# ArduinoUnoShield.net
KiCad netlist of a schematic drawn in Altium Designer
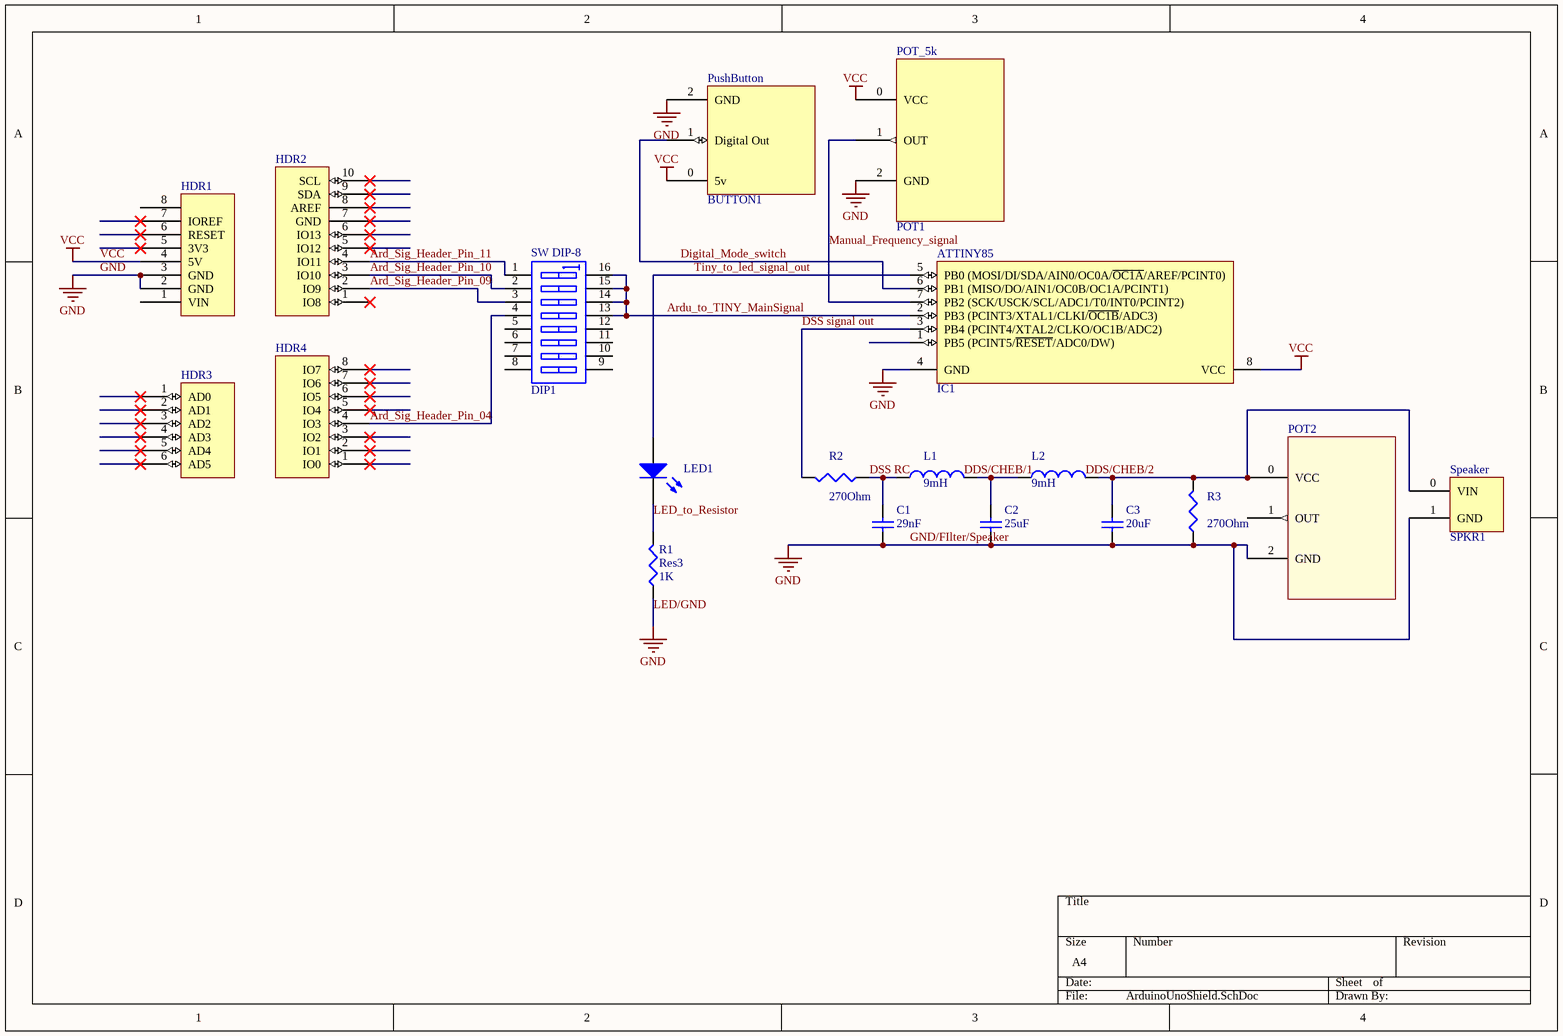
[diagram p0: ArduinoUnoShield.SchDoc]

(export (version "E")
  (design (tool "Eeschema 10.0.6"))
  (components
    (comp (ref "ATTINY85")
      (value "IC1")
      (footprint "DIP-8")
      (fields (field (name "PUBLISHER") "Altium Limited"))
      (libsource (lib "Atmel Microcontroller 8-Bit tinyAVR") (part "ATtiny85-20PU"))
    )
    (comp (ref "C1")
      (value "29nF")
      (footprint "1608[0603]")
      (description "Capacitor (Semiconductor SIM Model)")
      (fields (field (name "Comment") "Cap Semi") (field (name "PUBLISHER") "Altium Limited"))
      (libsource (lib "Miscellaneous Devices") (part "Cap Semi"))
    )
    (comp (ref "C2")
      (value "25uF")
      (footprint "1608[0603]")
      (description "Capacitor (Semiconductor SIM Model)")
      (fields (field (name "Comment") "Cap Semi") (field (name "PUBLISHER") "Altium Limited"))
      (libsource (lib "Miscellaneous Devices") (part "Cap Semi"))
    )
    (comp (ref "C3")
      (value "20uF")
      (footprint "1608[0603]")
      (description "Capacitor (Semiconductor SIM Model)")
      (fields (field (name "Comment") "Cap Semi") (field (name "PUBLISHER") "Altium Limited"))
      (libsource (lib "Miscellaneous Devices") (part "Cap Semi"))
    )
    (comp (ref "HDR1")
      (value "POWER_UNO")
      (footprint "Header 8x1 8.5mm")
      (libsource (lib "Header") (part "POWER_UNO"))
    )
    (comp (ref "HDR2")
      (value "IOH")
      (footprint "Header:Header 10x1 8.5mm")
      (libsource (lib "Header") (part "IOH"))
    )
    (comp (ref "HDR3")
      (value "AD")
      (footprint "Header:Header 6x1 8.5mm")
      (libsource (lib "Header") (part "AD"))
    )
    (comp (ref "HDR4") (value "IOL") (footprint "Header 8x1 8.5mm") (libsource (lib "Header") (part "IOL")))
    (comp (ref "L1")
      (value "9mH")
      (footprint "AXIAL-0.3")
      (description "Inductor")
      (fields (field (name "PUBLISHER") "Altium Limited"))
      (libsource (lib "Miscellaneous Devices") (part "Inductor"))
    )
    (comp (ref "L2")
      (value "9mH")
      (footprint "AXIAL-0.3")
      (description "Inductor")
      (fields (field (name "PUBLISHER") "Altium Limited"))
      (libsource (lib "Miscellaneous Devices") (part "Inductor"))
    )
    (comp (ref "LED1")
      (value "LED1")
      (footprint "LED-1")
      (description "Typical RED GaAs LED")
      (fields (field (name "PUBLISHER") "Altium Limited"))
      (libsource (lib "Miscellaneous Devices") (part "LED1"))
    )
    (comp (ref "POT2")
      (value "Component_1")
      (footprint "POT Footprint_Rev_1")
      (description "5k RES")
      (libsource (lib "PotLib_Rev_5") (part "Component_1"))
    )
    (comp (ref "POT_5k")
      (value "POT1")
      (footprint "POT Footprint_Rev_1")
      (description "5k RES")
      (libsource (lib "PotLib_Rev_5") (part "Component_1"))
    )
    (comp (ref "PushButton")
      (value "BUTTON1")
      (footprint "PushButtonFrame")
      (libsource (lib "Pushbutton_V_5") (part "PushButton"))
    )
    (comp (ref "R1")
      (value "Res3")
      (footprint "J1-0603")
      (description "Resistor")
      (fields (field (name "ALTIUM_VALUE") "1K") (field (name "PUBLISHER") "Altium Limited"))
      (libsource (lib "Miscellaneous Devices") (part "Res3"))
    )
    (comp (ref "R2")
      (value "270Ohm")
      (footprint "J1-0603")
      (description "Resistor")
      (fields (field (name "Comment") "Res3") (field (name "PUBLISHER") "Altium Limited"))
      (libsource (lib "Miscellaneous Devices") (part "Res3"))
    )
    (comp (ref "R3")
      (value "270Ohm")
      (footprint "J1-0603")
      (description "Resistor")
      (fields (field (name "Comment") "Res3") (field (name "PUBLISHER") "Altium Limited"))
      (libsource (lib "Miscellaneous Devices") (part "Res3"))
    )
    (comp (ref "Speaker")
      (value "SPKR1")
      (footprint "PCBComponent_1")
      (libsource (lib "Schlib1_rev_01") (part "Component_1"))
    )
    (comp (ref "SW DIP-8")
      (value "DIP1")
      (footprint "DIP_SW_8WAY_SMD")
      (description "DIP Switch, 8 Position, SPST")
      (fields (field (name "PUBLISHER") "Altium Limited"))
      (libsource (lib "Miscellaneous Devices") (part "SW DIP-8"))
    )
  )
  (nets
    (net (code "2") (name "/Ard_Sig_Header_Pin_04") (class "Default")
      (node (ref "HDR4") (pin "4") (pinfunction "IO3_4") (pintype "bidirectional"))
      (node (ref "SW DIP-8") (pin "4") (pinfunction "A4_4") (pintype "passive"))
    )
    (net (code "3") (name "/Ard_Sig_Header_Pin_09") (class "Default")
      (node (ref "HDR2") (pin "2") (pinfunction "IO9_2") (pintype "bidirectional"))
      (node (ref "SW DIP-8") (pin "3") (pinfunction "A3_3") (pintype "passive"))
    )
    (net (code "4") (name "/Ard_Sig_Header_Pin_10") (class "Default")
      (node (ref "HDR2") (pin "3") (pinfunction "IO10_3") (pintype "bidirectional"))
      (node (ref "SW DIP-8") (pin "2") (pinfunction "A2_2") (pintype "passive"))
    )
    (net (code "5") (name "/Ard_Sig_Header_Pin_11") (class "Default")
      (node (ref "HDR2") (pin "4") (pinfunction "IO11_4") (pintype "bidirectional"))
      (node (ref "SW DIP-8") (pin "1") (pinfunction "A1_1") (pintype "passive"))
    )
    (net (code "6") (name "/Ardu_to_TINY_MainSignal") (class "Default")
      (node (ref "ATTINY85") (pin "2") (pinfunction "PB3_(PCINT3/XTAL1/CLKI/~{OC1B}/ADC3)_2") (pintype "bidirectional"))
      (node (ref "SW DIP-8") (pin "13") (pinfunction "B4_13") (pintype "passive"))
      (node (ref "SW DIP-8") (pin "14") (pinfunction "B3_14") (pintype "passive"))
      (node (ref "SW DIP-8") (pin "15") (pinfunction "B2_15") (pintype "passive"))
      (node (ref "SW DIP-8") (pin "16") (pinfunction "B1_16") (pintype "passive"))
    )
    (net (code "9") (name "/DSS RC") (class "Default")
      (node (ref "C1") (pin "2") (pinfunction "2_2") (pintype "passive"))
      (node (ref "L1") (pin "1") (pinfunction "1_1") (pintype "passive"))
      (node (ref "R2") (pin "1") (pinfunction "1_1") (pintype "passive"))
    )
    (net (code "10") (name "/DSS signal out") (class "Default")
      (node (ref "ATTINY85") (pin "3") (pinfunction "PB4_(PCINT4/XTAL2/CLKO/OC1B/ADC2)_3") (pintype "bidirectional"))
      (node (ref "R2") (pin "2") (pinfunction "2_2") (pintype "passive"))
    )
    (net (code "11") (name "/Digital_Mode_switch") (class "Default")
      (node (ref "ATTINY85") (pin "6") (pinfunction "PB1_(MISO/DO/AIN1/OC0B/OC1A/PCINT1)_6") (pintype "bidirectional"))
      (node (ref "PushButton") (pin "1") (pinfunction "Digital_Out_1") (pintype "bidirectional"))
    )
    (net (code "12") (name "/LED_to_Resistor") (class "Default")
      (node (ref "LED1") (pin "2") (pinfunction "K_2") (pintype "passive"))
      (node (ref "R1") (pin "2") (pinfunction "2_2") (pintype "passive"))
    )
    (net (code "13") (name "/Manual_Frequency_signal") (class "Default")
      (node (ref "ATTINY85") (pin "7") (pinfunction "PB2_(SCK/USCK/SCL/ADC1/T0/INT0/PCINT2)_7") (pintype "bidirectional"))
      (node (ref "POT_5k") (pin "1") (pinfunction "OUT_1") (pintype "output"))
    )
    (net (code "14") (name "/Tiny_to_led_signal_out") (class "Default")
      (node (ref "ATTINY85") (pin "5") (pinfunction "PB0_(MOSI/DI/SDA/AIN0/OC0A/~{OC1A}/AREF/PCINT0)_5") (pintype "bidirectional"))
      (node (ref "LED1") (pin "1") (pinfunction "A_1") (pintype "passive"))
    )
    (net (code "15") (name "GND") (class "Default")
      (node (ref "ATTINY85") (pin "4") (pinfunction "GND_4") (pintype "power_in"))
      (node (ref "C1") (pin "1") (pinfunction "1_1") (pintype "passive"))
      (node (ref "C2") (pin "1") (pinfunction "1_1") (pintype "passive"))
      (node (ref "C3") (pin "1") (pinfunction "1_1") (pintype "passive"))
      (node (ref "HDR1") (pin "2") (pinfunction "GND_2") (pintype "power_in"))
      (node (ref "HDR1") (pin "3") (pinfunction "GND_3") (pintype "power_in"))
      (node (ref "POT2") (pin "2") (pinfunction "GND_2") (pintype "power_in"))
      (node (ref "POT_5k") (pin "2") (pinfunction "GND_2") (pintype "power_in"))
      (node (ref "PushButton") (pin "2") (pinfunction "GND_2") (pintype "power_in"))
      (node (ref "R1") (pin "1") (pinfunction "1_1") (pintype "passive"))
      (node (ref "R3") (pin "1") (pinfunction "1_1") (pintype "passive"))
      (node (ref "Speaker") (pin "1") (pinfunction "GND_1") (pintype "power_in"))
    )
    (net (code "16") (name "Net-(C2-Pad2)") (class "Default")
      (node (ref "C2") (pin "2") (pinfunction "2_2") (pintype "passive"))
      (node (ref "L1") (pin "2") (pinfunction "2_2") (pintype "passive"))
      (node (ref "L2") (pin "1") (pinfunction "1_1") (pintype "passive"))
    )
    (net (code "17") (name "Net-(POT2-VCC)") (class "Default")
      (node (ref "C3") (pin "2") (pinfunction "2_2") (pintype "passive"))
      (node (ref "L2") (pin "2") (pinfunction "2_2") (pintype "passive"))
      (node (ref "POT2") (pin "0") (pinfunction "VCC_0") (pintype "power_in"))
      (node (ref "R3") (pin "2") (pinfunction "2_2") (pintype "passive"))
      (node (ref "Speaker") (pin "0") (pinfunction "VIN_0") (pintype "power_in"))
    )
    (net (code "18") (name "VCC") (class "Default")
      (node (ref "ATTINY85") (pin "8") (pinfunction "VCC_8") (pintype "power_in"))
      (node (ref "HDR1") (pin "4") (pinfunction "5V_4") (pintype "power_in"))
      (node (ref "POT_5k") (pin "0") (pinfunction "VCC_0") (pintype "power_in"))
      (node (ref "PushButton") (pin "0") (pinfunction "5v_0") (pintype "power_in"))
    )
    (net (code "19") (name "unconnected-(ATTINY85-PB5_(PCINT5{slash}~{RESET}{slash}ADC0{slash}DW)-Pad1)") (class "Default")
      (node (ref "ATTINY85") (pin "1") (pinfunction "PB5_(PCINT5/~{RESET}/ADC0/DW)_1") (pintype "bidirectional"))
    )
    (net (code "20") (name "unconnected-(HDR1-3V3-Pad5)") (class "Default")
      (node (ref "HDR1") (pin "5") (pinfunction "3V3_5") (pintype "power_in+no_connect"))
    )
    (net (code "21") (name "unconnected-(HDR1-IOREF-Pad7)") (class "Default")
      (node (ref "HDR1") (pin "7") (pinfunction "IOREF_7") (pintype "power_in+no_connect"))
    )
    (net (code "22") (name "unconnected-(HDR1-Pad8)") (class "Default")
      (node (ref "HDR1") (pin "8") (pintype "passive"))
    )
    (net (code "23") (name "unconnected-(HDR1-RESET-Pad6)") (class "Default")
      (node (ref "HDR1") (pin "6") (pinfunction "RESET_6") (pintype "passive+no_connect"))
    )
    (net (code "24") (name "unconnected-(HDR1-VIN-Pad1)") (class "Default")
      (node (ref "HDR1") (pin "1") (pinfunction "VIN_1") (pintype "power_in"))
    )
    (net (code "25") (name "unconnected-(HDR2-AREF-Pad8)") (class "Default")
      (node (ref "HDR2") (pin "8") (pinfunction "AREF_8") (pintype "passive+no_connect"))
    )
    (net (code "26") (name "unconnected-(HDR2-GND-Pad7)") (class "Default")
      (node (ref "HDR2") (pin "7") (pinfunction "GND_7") (pintype "power_in+no_connect"))
    )
    (net (code "27") (name "unconnected-(HDR2-IO8-Pad1)") (class "Default")
      (node (ref "HDR2") (pin "1") (pinfunction "IO8_1") (pintype "bidirectional+no_connect"))
    )
    (net (code "28") (name "unconnected-(HDR2-IO12-Pad5)") (class "Default")
      (node (ref "HDR2") (pin "5") (pinfunction "IO12_5") (pintype "bidirectional+no_connect"))
    )
    (net (code "29") (name "unconnected-(HDR2-IO13-Pad6)") (class "Default")
      (node (ref "HDR2") (pin "6") (pinfunction "IO13_6") (pintype "bidirectional+no_connect"))
    )
    (net (code "30") (name "unconnected-(HDR2-SCL-Pad10)") (class "Default")
      (node (ref "HDR2") (pin "10") (pinfunction "SCL_10") (pintype "bidirectional+no_connect"))
    )
    (net (code "31") (name "unconnected-(HDR2-SDA-Pad9)") (class "Default")
      (node (ref "HDR2") (pin "9") (pinfunction "SDA_9") (pintype "bidirectional+no_connect"))
    )
    (net (code "32") (name "unconnected-(HDR3-AD0-Pad1)") (class "Default")
      (node (ref "HDR3") (pin "1") (pinfunction "AD0_1") (pintype "bidirectional+no_connect"))
    )
    (net (code "33") (name "unconnected-(HDR3-AD1-Pad2)") (class "Default")
      (node (ref "HDR3") (pin "2") (pinfunction "AD1_2") (pintype "bidirectional+no_connect"))
    )
    (net (code "34") (name "unconnected-(HDR3-AD2-Pad3)") (class "Default")
      (node (ref "HDR3") (pin "3") (pinfunction "AD2_3") (pintype "bidirectional+no_connect"))
    )
    (net (code "35") (name "unconnected-(HDR3-AD3-Pad4)") (class "Default")
      (node (ref "HDR3") (pin "4") (pinfunction "AD3_4") (pintype "bidirectional+no_connect"))
    )
    (net (code "36") (name "unconnected-(HDR3-AD4-Pad5)") (class "Default")
      (node (ref "HDR3") (pin "5") (pinfunction "AD4_5") (pintype "bidirectional+no_connect"))
    )
    (net (code "37") (name "unconnected-(HDR3-AD5-Pad6)") (class "Default")
      (node (ref "HDR3") (pin "6") (pinfunction "AD5_6") (pintype "bidirectional+no_connect"))
    )
    (net (code "38") (name "unconnected-(HDR4-IO0-Pad1)") (class "Default")
      (node (ref "HDR4") (pin "1") (pinfunction "IO0_1") (pintype "bidirectional+no_connect"))
    )
    (net (code "39") (name "unconnected-(HDR4-IO1-Pad2)") (class "Default")
      (node (ref "HDR4") (pin "2") (pinfunction "IO1_2") (pintype "bidirectional+no_connect"))
    )
    (net (code "40") (name "unconnected-(HDR4-IO2-Pad3)") (class "Default")
      (node (ref "HDR4") (pin "3") (pinfunction "IO2_3") (pintype "bidirectional+no_connect"))
    )
    (net (code "41") (name "unconnected-(HDR4-IO4-Pad5)") (class "Default")
      (node (ref "HDR4") (pin "5") (pinfunction "IO4_5") (pintype "bidirectional+no_connect"))
    )
    (net (code "42") (name "unconnected-(HDR4-IO5-Pad6)") (class "Default")
      (node (ref "HDR4") (pin "6") (pinfunction "IO5_6") (pintype "bidirectional+no_connect"))
    )
    (net (code "43") (name "unconnected-(HDR4-IO6-Pad7)") (class "Default")
      (node (ref "HDR4") (pin "7") (pinfunction "IO6_7") (pintype "bidirectional+no_connect"))
    )
    (net (code "44") (name "unconnected-(HDR4-IO7-Pad8)") (class "Default")
      (node (ref "HDR4") (pin "8") (pinfunction "IO7_8") (pintype "bidirectional+no_connect"))
    )
    (net (code "45") (name "unconnected-(POT2-OUT-Pad1)") (class "Default")
      (node (ref "POT2") (pin "1") (pinfunction "OUT_1") (pintype "output"))
    )
    (net (code "46") (name "unconnected-(SW DIP-8-A5-Pad5)") (class "Default")
      (node (ref "SW DIP-8") (pin "5") (pinfunction "A5_5") (pintype "passive"))
    )
    (net (code "47") (name "unconnected-(SW DIP-8-A6-Pad6)") (class "Default")
      (node (ref "SW DIP-8") (pin "6") (pinfunction "A6_6") (pintype "passive"))
    )
    (net (code "48") (name "unconnected-(SW DIP-8-A7-Pad7)") (class "Default")
      (node (ref "SW DIP-8") (pin "7") (pinfunction "A7_7") (pintype "passive"))
    )
    (net (code "49") (name "unconnected-(SW DIP-8-A8-Pad8)") (class "Default")
      (node (ref "SW DIP-8") (pin "8") (pinfunction "A8_8") (pintype "passive"))
    )
    (net (code "50") (name "unconnected-(SW DIP-8-B5-Pad12)") (class "Default")
      (node (ref "SW DIP-8") (pin "12") (pinfunction "B5_12") (pintype "passive"))
    )
    (net (code "51") (name "unconnected-(SW DIP-8-B6-Pad11)") (class "Default")
      (node (ref "SW DIP-8") (pin "11") (pinfunction "B6_11") (pintype "passive"))
    )
    (net (code "52") (name "unconnected-(SW DIP-8-B7-Pad10)") (class "Default")
      (node (ref "SW DIP-8") (pin "10") (pinfunction "B7_10") (pintype "passive"))
    )
    (net (code "53") (name "unconnected-(SW DIP-8-B8-Pad9)") (class "Default")
      (node (ref "SW DIP-8") (pin "9") (pinfunction "B8_9") (pintype "passive"))
    )
  )
)
